# RS_MCU.net
KiCad netlist of a schematic drawn in Altium Designer
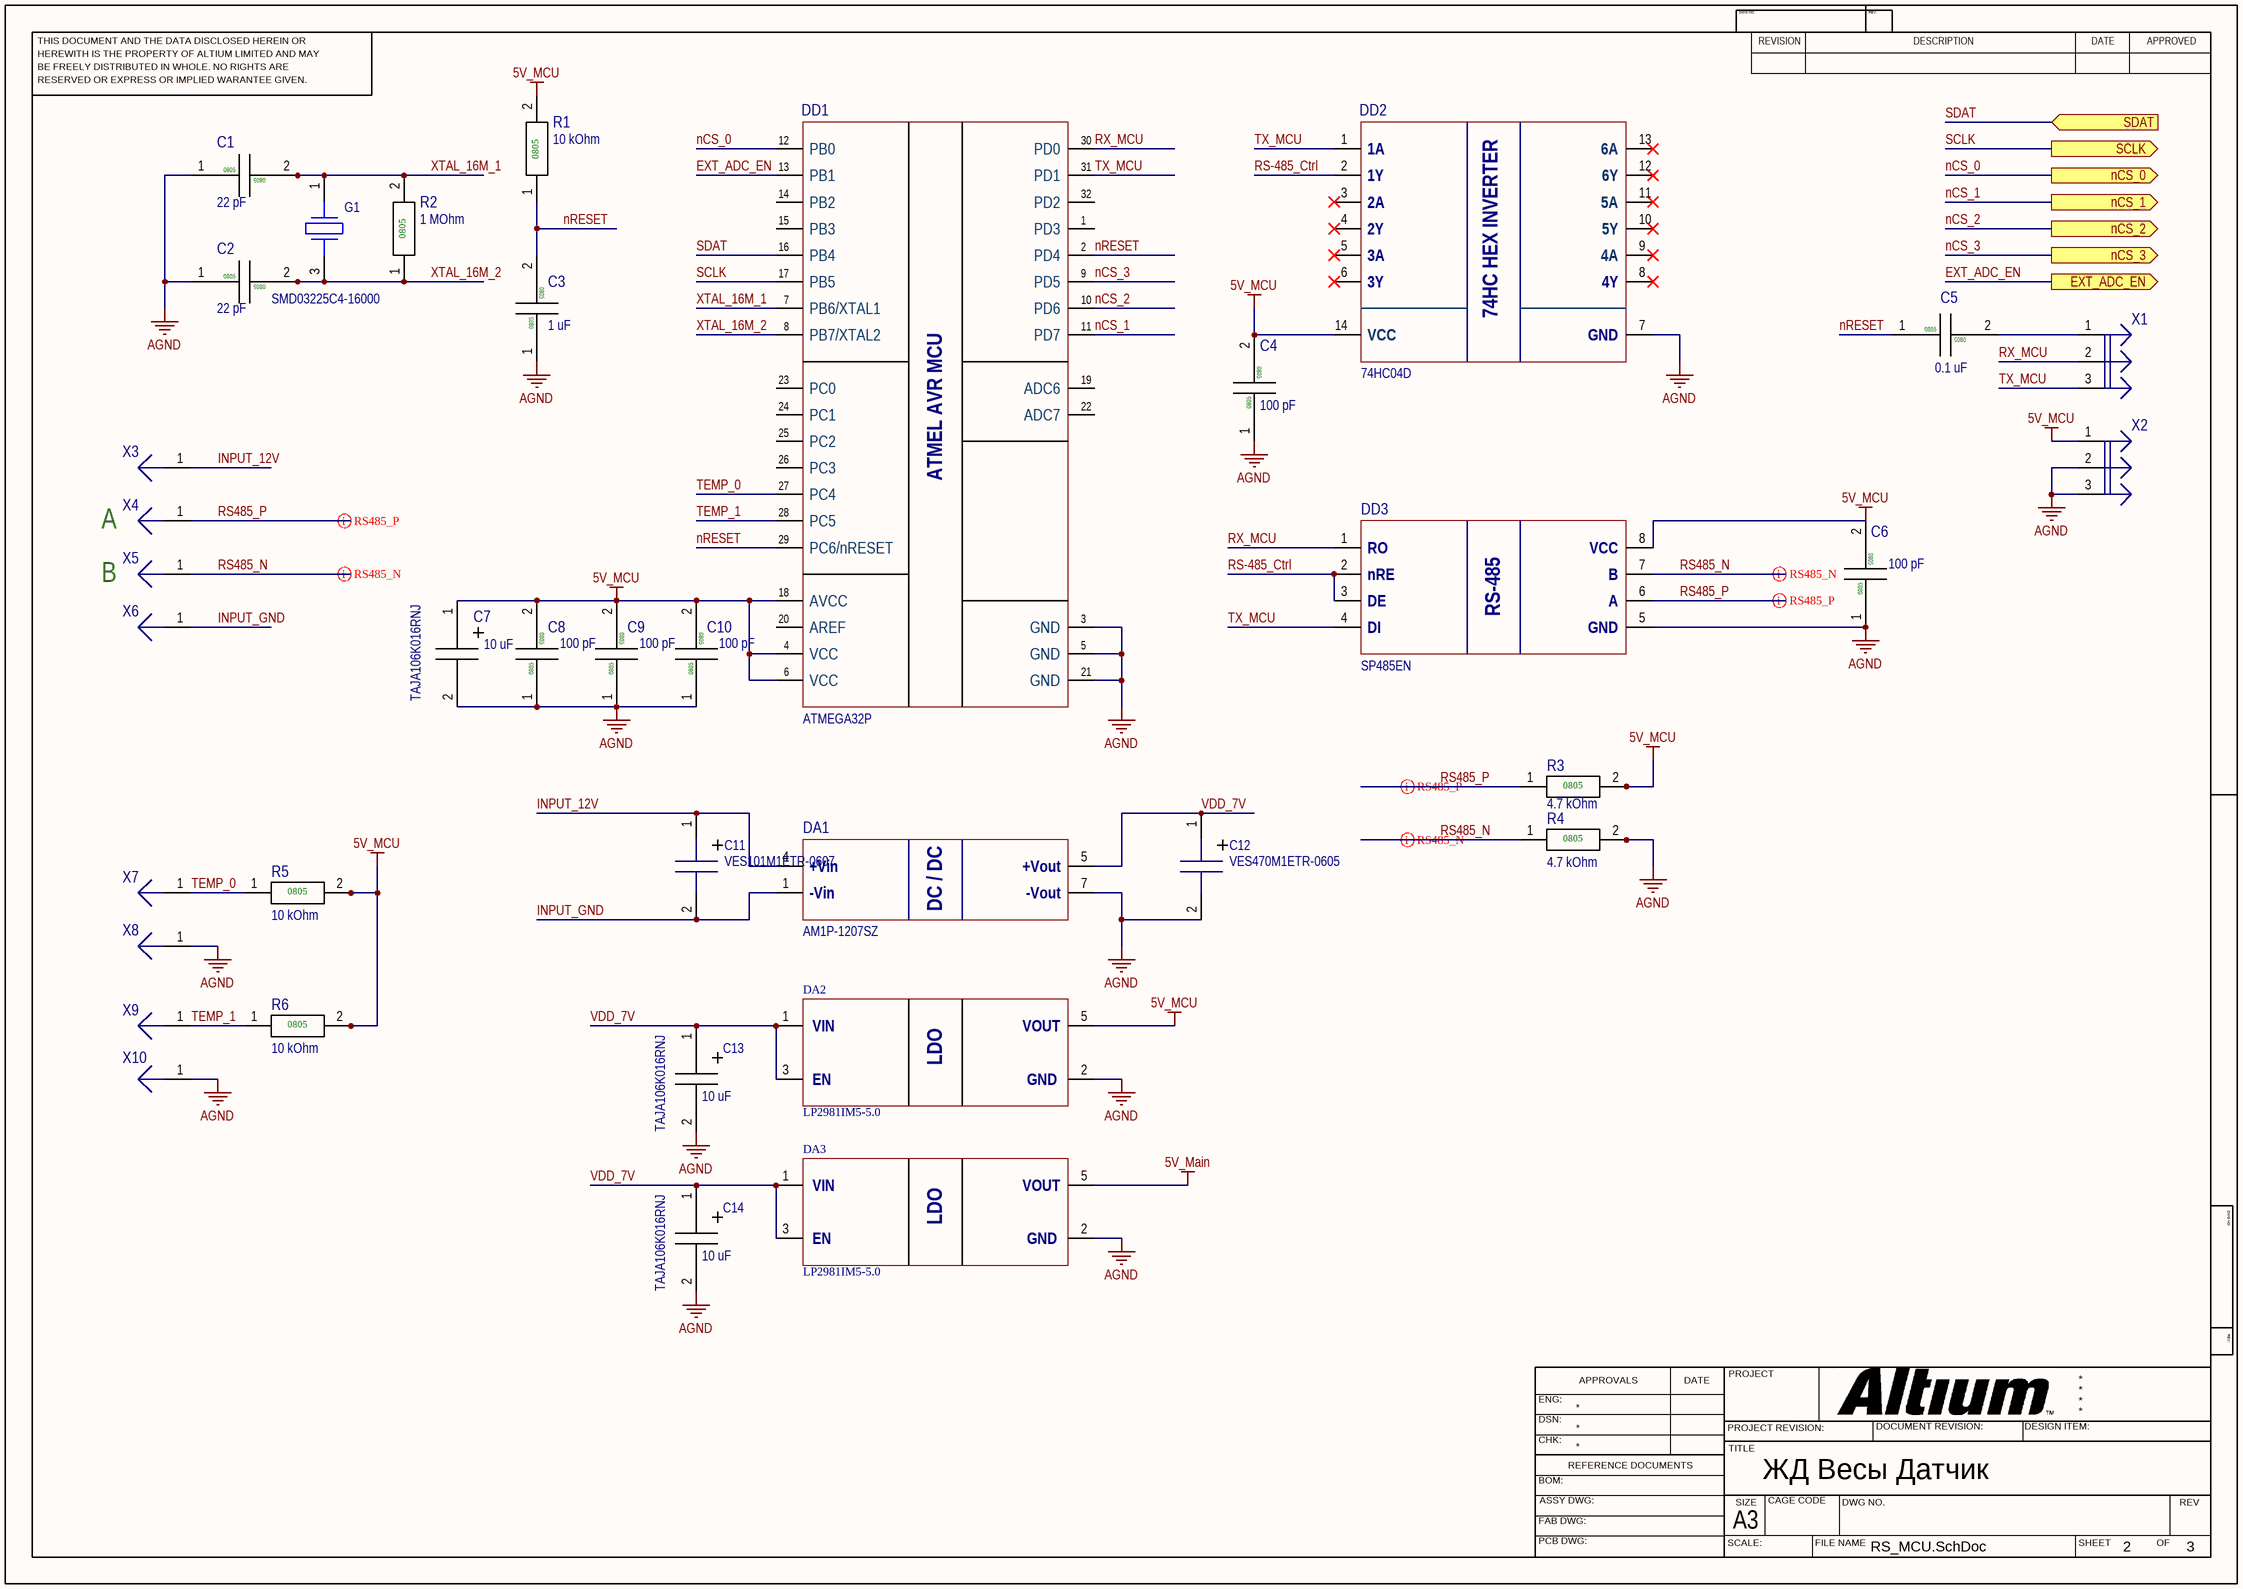
[diagram p0: RS_MCU.SchDoc]

(export (version "E")
  (design (tool "Eeschema 10.0.6"))
  (components
    (comp (ref "C1")
      (value "22 pF")
      (footprint "CAP: 0805")
      (description "50V 22pF C0G ±5% 0805 Multilayer Ceramic Capacitors MLCC - SMD/SMT ROHS")
      (fields
        (field (name "MANUFACTURER") "FH(Guangdong Fenghua Advanced Tech)")
        (field (name "VOLTAGE") "50 V")
      )
      (libsource (lib "CAP_Ceramic_0805(JLCPCB)") (part "22 pF 50V 5%"))
    )
    (comp (ref "C2")
      (value "22 pF")
      (footprint "CAP: 0805")
      (description "50V 22pF C0G ±5% 0805 Multilayer Ceramic Capacitors MLCC - SMD/SMT ROHS")
      (fields
        (field (name "MANUFACTURER") "FH(Guangdong Fenghua Advanced Tech)")
        (field (name "VOLTAGE") "50 V")
      )
      (libsource (lib "CAP_Ceramic_0805(JLCPCB)") (part "22 pF 50V 5%"))
    )
    (comp (ref "C3")
      (value "1 uF")
      (footprint "CAP: 0805")
      (description "Ceramic capacitor 0805 surface mount")
      (fields (field (name "MANUFACTURER") "Samsung Electro-Mechanics") (field (name "VOLTAGE") "50 V"))
      (libsource (lib "CAP_Ceramic_0805(JLCPCB)") (part "1 uF 50V 20%"))
    )
    (comp (ref "C4")
      (value "100 pF")
      (footprint "CAP: 0805")
      (description "Ceramic capacitor 0805 surface mount")
      (fields (field (name "MANUFACTURER") "Samsung Electro-Mechanics") (field (name "VOLTAGE") "50 V"))
      (libsource (lib "CAP_Ceramic_0805(JLCPCB)") (part "100 pF 50V 5%"))
    )
    (comp (ref "C5")
      (value "0.1 uF")
      (footprint "CAP: 0805")
      (description "Ceramic capacitor 0805 surface mount")
      (fields (field (name "MANUFACTURER") "Yageo") (field (name "VOLTAGE") "50 V"))
      (libsource (lib "CAP_Ceramic_0805(JLCPCB)") (part "0.1 uF 50V 20%"))
    )
    (comp (ref "C6")
      (value "100 pF")
      (footprint "CAP: 0805")
      (description "Ceramic capacitor 0805 surface mount")
      (fields (field (name "MANUFACTURER") "Samsung Electro-Mechanics") (field (name "VOLTAGE") "50 V"))
      (libsource (lib "CAP_Ceramic_0805(JLCPCB)") (part "100 pF 50V 5%"))
    )
    (comp (ref "C7")
      (value "TAJA106K016RNJ")
      (footprint "CAP: TANTAL-A")
      (description "10uF 16V 3Ω@100kHz -55℃~+125℃ ±10% CASE-A_3216 Tantalum Capacitors ROHS")
      (fields
        (field (name "MANUFACTURER") "AVX")
        (field (name "TOLERANCE") "10%")
        (field (name "CAPVALUE") "10 uF")
      )
      (libsource (lib "CAP_Tantalum") (part "10uF 16V 10%"))
    )
    (comp (ref "C8")
      (value "100 pF")
      (footprint "CAP: 0805")
      (description "Ceramic capacitor 0805 surface mount")
      (fields (field (name "MANUFACTURER") "Samsung Electro-Mechanics") (field (name "VOLTAGE") "50 V"))
      (libsource (lib "CAP_Ceramic_0805(JLCPCB)") (part "100 pF 50V 5%"))
    )
    (comp (ref "C9")
      (value "100 pF")
      (footprint "CAP: 0805")
      (description "Ceramic capacitor 0805 surface mount")
      (fields (field (name "MANUFACTURER") "Samsung Electro-Mechanics") (field (name "VOLTAGE") "50 V"))
      (libsource (lib "CAP_Ceramic_0805(JLCPCB)") (part "100 pF 50V 5%"))
    )
    (comp (ref "C10")
      (value "100 pF")
      (footprint "CAP: 0805")
      (description "Ceramic capacitor 0805 surface mount")
      (fields (field (name "MANUFACTURER") "Samsung Electro-Mechanics") (field (name "VOLTAGE") "50 V"))
      (libsource (lib "CAP_Ceramic_0805(JLCPCB)") (part "100 pF 50V 5%"))
    )
    (comp (ref "C11")
      (value "VES101M1ETR-0607")
      (footprint "CAPAE-C")
      (fields
        (field (name "LCSC PART NUMBER") "C176675")
        (field (name "MANUFACTURER") "Lelon")
        (field (name "VOLTAGE") "25 V")
      )
      (libsource (lib "CAP_Aluminium_SMD") (part "47uF 25V"))
    )
    (comp (ref "C12")
      (value "VES470M1ETR-0605")
      (footprint "CAPAE-C")
      (fields
        (field (name "LCSC PART NUMBER") "C176679")
        (field (name "MANUFACTURER") "Lelon")
        (field (name "VOLTAGE") "25 V")
      )
      (libsource (lib "CAP_Aluminium_SMD") (part "47uF 25V"))
    )
    (comp (ref "C13")
      (value "TAJA106K016RNJ")
      (footprint "CAP: TANTAL-A")
      (description "10uF 16V 3Ω@100kHz -55℃~+125℃ ±10% CASE-A_3216 Tantalum Capacitors ROHS")
      (fields
        (field (name "MANUFACTURER") "AVX")
        (field (name "TOLERANCE") "10%")
        (field (name "CAPVALUE") "10 uF")
      )
      (libsource (lib "CAP_Tantalum") (part "10uF 16V 10%"))
    )
    (comp (ref "C14")
      (value "TAJA106K016RNJ")
      (footprint "CAP: TANTAL-A")
      (description "10uF 16V 3Ω@100kHz -55℃~+125℃ ±10% CASE-A_3216 Tantalum Capacitors ROHS")
      (fields
        (field (name "MANUFACTURER") "AVX")
        (field (name "TOLERANCE") "10%")
        (field (name "CAPVALUE") "10 uF")
      )
      (libsource (lib "CAP_Tantalum") (part "10uF 16V 10%"))
    )
    (comp (ref "DA1")
      (value "AM1P-1207SZ")
      (footprint "MOD_AM1P-Z")
      (description "1W, FIXED INPUT, ISOLATED & REGULATED  SINGLE OUTPUT DC-DC CONVERTER")
      (fields (field (name "LCSC PART NUMBER") "--") (field (name "MANUFACTURER") "AIMTEC"))
      (libsource (lib "ICs_Power(Isolated)") (part "AM1P-1207SZ"))
    )
    (comp (ref "DA2")
      (value "LP2981IM5-5.0")
      (footprint "SOT-23-5")
      (description "Micropower 100-mA Ultralow Dropout Regulator in SOT-23 Package")
      (fields
        (field (name "MANUFACTURER") "Texas Instruments Incorporated")
        (field (name "LCSC PART NUMBER") "C3749295")
      )
      (libsource (lib "ICs_Power(Linear)") (part "LP2981IM5-5.0"))
    )
    (comp (ref "DA3")
      (value "LP2981IM5-5.0")
      (footprint "SOT-23-5")
      (description "Micropower 100-mA Ultralow Dropout Regulator in SOT-23 Package")
      (fields
        (field (name "MANUFACTURER") "Texas Instruments Incorporated")
        (field (name "LCSC PART NUMBER") "C3749295")
      )
      (libsource (lib "ICs_Power(Linear)") (part "LP2981IM5-5.0"))
    )
    (comp (ref "DD1")
      (value "ATMEGA32P")
      (footprint "32-LQFP")
      (fields (field (name "MANUFACTURER") "Atmel"))
      (libsource (lib "ICs_MCU") (part "ATMega238P"))
    )
    (comp (ref "DD2")
      (value "74HC04D")
      (footprint "14-SOIC")
      (fields (field (name "LCSC PART NUMBER") "C86613") (field (name "MANUFACTURER") "Shenzhen Fuman Elec"))
      (libsource (lib "ICs_Logic") (part "74HC04D"))
    )
    (comp (ref "DD3")
      (value "SP485EN")
      (footprint "8-SOIC")
      (description "Enhanced Low Power Half-Duplex\r\nRS-485 Transceivers")
      (fields
        (field (name "MANUFACTURER") "UMW(Youtai Semiconductor Co., Ltd.")
        (field (name "LCSC PART NUMBER") "C23492")
      )
      (libsource (lib "ICs_Interface") (part "SP485EN"))
    )
    (comp (ref "G1")
      (value "SMD03225C4-16000")
      (footprint "OSC: 3225")
      (description "Crystals WE-XTAL 16.0MHz 50ppm 13.4 x 4.9mm")
      (fields (field (name "MANUFACTURER") "SDE"))
      (libsource (lib "Crystals") (part "SMD03225C4-16000"))
    )
    (comp (ref "R1")
      (value "10 kOhm")
      (footprint "RES: 0805")
      (description "LEAD-FREE THICK FILM CHIP RESISTORS")
      (fields (field (name "MANUFACTURER") "Uniroyal Elec") (field (name "TOLERANCE") "1%"))
      (libsource (lib "") (part "10k 1% 1/8W_1"))
    )
    (comp (ref "R2")
      (value "1 MOhm")
      (footprint "RES: 0805")
      (description "LEAD-FREE THICK FILM CHIP RESISTORS")
      (fields (field (name "MANUFACTURER") "Uniroyal Elec") (field (name "TOLERANCE") "1%"))
      (libsource (lib "RES_SMD_0805(JLCPCB)") (part "1M 1% 1/8W"))
    )
    (comp (ref "R3")
      (value "4.7 kOhm")
      (footprint "RES: 0805")
      (description "LEAD-FREE THICK FILM CHIP RESISTORS")
      (fields (field (name "MANUFACTURER") "Uniroyal Elec") (field (name "TOLERANCE") "1%"))
      (libsource (lib "RES_SMD_0805(JLCPCB)") (part "4.7k 1% 1/8W"))
    )
    (comp (ref "R4")
      (value "4.7 kOhm")
      (footprint "RES: 0805")
      (description "LEAD-FREE THICK FILM CHIP RESISTORS")
      (fields (field (name "MANUFACTURER") "Uniroyal Elec") (field (name "TOLERANCE") "1%"))
      (libsource (lib "RES_SMD_0805(JLCPCB)") (part "4.7k 1% 1/8W"))
    )
    (comp (ref "R5")
      (value "10 kOhm")
      (footprint "RES: 0805")
      (description "LEAD-FREE THICK FILM CHIP RESISTORS")
      (fields (field (name "MANUFACTURER") "Uniroyal Elec") (field (name "TOLERANCE") "1%"))
      (libsource (lib "RES_SMD_0805(JLCPCB)") (part "10k 1% 1/8W"))
    )
    (comp (ref "R6")
      (value "10 kOhm")
      (footprint "RES: 0805")
      (description "LEAD-FREE THICK FILM CHIP RESISTORS")
      (fields (field (name "MANUFACTURER") "Uniroyal Elec") (field (name "TOLERANCE") "1%"))
      (libsource (lib "RES_SMD_0805(JLCPCB)") (part "10k 1% 1/8W"))
    )
    (comp (ref "X1")
      (value "PLS-1X3Pin 2.54")
      (footprint "CON: PLS-3")
      (libsource (lib "Connectors&PinHeaders") (part "PLS-1X3Pin 2.54"))
    )
    (comp (ref "X2")
      (value "PLS-1X3Pin 2.54")
      (footprint "CON: PLS-3")
      (libsource (lib "Connectors&PinHeaders") (part "PLS-1X3Pin 2.54"))
    )
    (comp (ref "X3")
      (value "PowerSingleHole")
      (footprint "PowerSingle")
      (libsource (lib "Connectors&PinHeaders") (part "PowerSingleHole"))
    )
    (comp (ref "X4")
      (value "PowerSingleHole")
      (footprint "PowerSingle")
      (libsource (lib "Connectors&PinHeaders") (part "PowerSingleHole"))
    )
    (comp (ref "X5")
      (value "PowerSingleHole")
      (footprint "PowerSingle")
      (libsource (lib "Connectors&PinHeaders") (part "PowerSingleHole"))
    )
    (comp (ref "X6")
      (value "PowerSingleHole")
      (footprint "PowerSingle")
      (libsource (lib "Connectors&PinHeaders") (part "PowerSingleHole"))
    )
    (comp (ref "X7")
      (value "PowerSingleHole")
      (footprint "PowerSingle")
      (libsource (lib "Connectors&PinHeaders") (part "PowerSingleHole"))
    )
    (comp (ref "X8")
      (value "PowerSingleHole")
      (footprint "PowerSingle")
      (libsource (lib "Connectors&PinHeaders") (part "PowerSingleHole"))
    )
    (comp (ref "X9")
      (value "PowerSingleHole")
      (footprint "PowerSingle")
      (libsource (lib "Connectors&PinHeaders") (part "PowerSingleHole"))
    )
    (comp (ref "X10")
      (value "PowerSingleHole")
      (footprint "PowerSingle")
      (libsource (lib "Connectors&PinHeaders") (part "PowerSingleHole"))
    )
  )
  (nets
    (net (code "1") (name "/EXT_ADC_EN") (class "Default")
      (node (ref "DD1") (pin "13") (pinfunction "PB1_13") (pintype "passive"))
    )
    (net (code "2") (name "/INPUT_12V") (class "Default")
      (node (ref "C11") (pin "1") (pintype "passive"))
      (node (ref "DA1") (pin "4") (pinfunction "+Vin_4") (pintype "passive"))
      (node (ref "X3") (pin "1") (pinfunction "1_1") (pintype "passive"))
    )
    (net (code "3") (name "/INPUT_GND") (class "Default")
      (node (ref "C11") (pin "2") (pintype "passive"))
      (node (ref "DA1") (pin "1") (pinfunction "-Vin_1") (pintype "passive"))
      (node (ref "X6") (pin "1") (pinfunction "1_1") (pintype "passive"))
    )
    (net (code "4") (name "/RS-485_Ctrl") (class "Default")
      (node (ref "DD2") (pin "2") (pinfunction "1Y_2") (pintype "passive"))
      (node (ref "DD3") (pin "2") (pinfunction "nRE_2") (pintype "passive"))
      (node (ref "DD3") (pin "3") (pinfunction "DE_3") (pintype "passive"))
    )
    (net (code "5") (name "/RS485_N") (class "Default")
      (node (ref "DD3") (pin "7") (pinfunction "B_7") (pintype "passive"))
      (node (ref "R4") (pin "1") (pintype "passive"))
      (node (ref "X5") (pin "1") (pinfunction "1_1") (pintype "passive"))
    )
    (net (code "6") (name "/RS485_P") (class "Default")
      (node (ref "DD3") (pin "6") (pinfunction "A_6") (pintype "passive"))
      (node (ref "R3") (pin "1") (pintype "passive"))
      (node (ref "X4") (pin "1") (pinfunction "1_1") (pintype "passive"))
    )
    (net (code "7") (name "/RX_MCU") (class "Default")
      (node (ref "DD1") (pin "30") (pinfunction "PD0_30") (pintype "passive"))
      (node (ref "DD3") (pin "1") (pinfunction "RO_1") (pintype "passive"))
      (node (ref "X1") (pin "2") (pinfunction "2_2") (pintype "passive"))
    )
    (net (code "8") (name "/SCLK") (class "Default")
      (node (ref "DD1") (pin "17") (pinfunction "PB5_17") (pintype "passive"))
    )
    (net (code "9") (name "/SDAT") (class "Default")
      (node (ref "DD1") (pin "16") (pinfunction "PB4_16") (pintype "passive"))
    )
    (net (code "10") (name "/TEMP_0") (class "Default")
      (node (ref "DD1") (pin "27") (pinfunction "PC4_27") (pintype "passive"))
      (node (ref "R5") (pin "1") (pintype "passive"))
      (node (ref "X7") (pin "1") (pinfunction "1_1") (pintype "passive"))
    )
    (net (code "11") (name "/TEMP_1") (class "Default")
      (node (ref "DD1") (pin "28") (pinfunction "PC5_28") (pintype "passive"))
      (node (ref "R6") (pin "1") (pintype "passive"))
      (node (ref "X9") (pin "1") (pinfunction "1_1") (pintype "passive"))
    )
    (net (code "12") (name "/TX_MCU") (class "Default")
      (node (ref "DD1") (pin "31") (pinfunction "PD1_31") (pintype "passive"))
      (node (ref "DD2") (pin "1") (pinfunction "1A_1") (pintype "passive"))
      (node (ref "DD3") (pin "4") (pinfunction "DI_4") (pintype "passive"))
      (node (ref "X1") (pin "3") (pinfunction "3_3") (pintype "passive"))
    )
    (net (code "13") (name "/VDD_7V") (class "Default")
      (node (ref "C12") (pin "1") (pintype "passive"))
      (node (ref "C13") (pin "1") (pintype "passive"))
      (node (ref "C14") (pin "1") (pintype "passive"))
      (node (ref "DA1") (pin "5") (pinfunction "+Vout_5") (pintype "passive"))
      (node (ref "DA2") (pin "1") (pinfunction "VIN_1") (pintype "passive"))
      (node (ref "DA2") (pin "3") (pinfunction "EN_3") (pintype "passive"))
      (node (ref "DA3") (pin "1") (pinfunction "VIN_1") (pintype "passive"))
      (node (ref "DA3") (pin "3") (pinfunction "EN_3") (pintype "passive"))
    )
    (net (code "14") (name "/XTAL_16M_1") (class "Default")
      (node (ref "C1") (pin "2") (pintype "passive"))
      (node (ref "DD1") (pin "7") (pinfunction "PB6/XTAL1_7") (pintype "passive"))
      (node (ref "G1") (pin "1") (pintype "passive"))
      (node (ref "R2") (pin "2") (pintype "passive"))
    )
    (net (code "15") (name "/XTAL_16M_2") (class "Default")
      (node (ref "C2") (pin "2") (pintype "passive"))
      (node (ref "DD1") (pin "8") (pinfunction "PB7/XTAL2_8") (pintype "passive"))
      (node (ref "G1") (pin "3") (pintype "passive"))
      (node (ref "R2") (pin "1") (pintype "passive"))
    )
    (net (code "16") (name "/nCS_0") (class "Default")
      (node (ref "DD1") (pin "12") (pinfunction "PB0_12") (pintype "passive"))
    )
    (net (code "17") (name "/nCS_1") (class "Default")
      (node (ref "DD1") (pin "11") (pinfunction "PD7_11") (pintype "passive"))
    )
    (net (code "18") (name "/nCS_2") (class "Default")
      (node (ref "DD1") (pin "10") (pinfunction "PD6_10") (pintype "passive"))
    )
    (net (code "19") (name "/nCS_3") (class "Default")
      (node (ref "DD1") (pin "9") (pinfunction "PD5_9") (pintype "passive"))
    )
    (net (code "20") (name "/nRESET") (class "Default")
      (node (ref "C3") (pin "2") (pintype "passive"))
      (node (ref "C5") (pin "1") (pintype "passive"))
      (node (ref "DD1") (pin "2") (pinfunction "PD4_2") (pintype "passive"))
      (node (ref "DD1") (pin "29") (pinfunction "PC6/nRESET_29") (pintype "passive"))
      (node (ref "R1") (pin "1") (pintype "passive"))
    )
    (net (code "21") (name "5V_MCU") (class "Default")
      (node (ref "C10") (pin "2") (pintype "passive"))
      (node (ref "C4") (pin "2") (pintype "passive"))
      (node (ref "C6") (pin "2") (pintype "passive"))
      (node (ref "C7") (pin "1") (pintype "passive"))
      (node (ref "C8") (pin "2") (pintype "passive"))
      (node (ref "C9") (pin "2") (pintype "passive"))
      (node (ref "DA2") (pin "5") (pinfunction "VOUT_5") (pintype "passive"))
      (node (ref "DD1") (pin "18") (pinfunction "AVCC_18") (pintype "passive"))
      (node (ref "DD1") (pin "4") (pinfunction "VCC_4") (pintype "passive"))
      (node (ref "DD1") (pin "6") (pinfunction "VCC_6") (pintype "passive"))
      (node (ref "DD2") (pin "14") (pinfunction "VCC_14") (pintype "passive"))
      (node (ref "DD3") (pin "8") (pinfunction "VCC_8") (pintype "passive"))
      (node (ref "R1") (pin "2") (pintype "passive"))
      (node (ref "R3") (pin "2") (pintype "passive"))
      (node (ref "R5") (pin "2") (pintype "passive"))
      (node (ref "R6") (pin "2") (pintype "passive"))
      (node (ref "X2") (pin "1") (pinfunction "1_1") (pintype "passive"))
    )
    (net (code "22") (name "5V_Main") (class "Default")
      (node (ref "DA3") (pin "5") (pinfunction "VOUT_5") (pintype "passive"))
    )
    (net (code "23") (name "AGND") (class "Default")
      (node (ref "C1") (pin "1") (pintype "passive"))
      (node (ref "C10") (pin "1") (pintype "passive"))
      (node (ref "C12") (pin "2") (pintype "passive"))
      (node (ref "C13") (pin "2") (pintype "passive"))
      (node (ref "C14") (pin "2") (pintype "passive"))
      (node (ref "C2") (pin "1") (pintype "passive"))
      (node (ref "C3") (pin "1") (pintype "passive"))
      (node (ref "C4") (pin "1") (pintype "passive"))
      (node (ref "C6") (pin "1") (pintype "passive"))
      (node (ref "C7") (pin "2") (pintype "passive"))
      (node (ref "C8") (pin "1") (pintype "passive"))
      (node (ref "C9") (pin "1") (pintype "passive"))
      (node (ref "DA1") (pin "7") (pinfunction "-Vout_7") (pintype "passive"))
      (node (ref "DA2") (pin "2") (pinfunction "GND_2") (pintype "passive"))
      (node (ref "DA3") (pin "2") (pinfunction "GND_2") (pintype "passive"))
      (node (ref "DD1") (pin "21") (pinfunction "GND_21") (pintype "passive"))
      (node (ref "DD1") (pin "3") (pinfunction "GND_3") (pintype "passive"))
      (node (ref "DD1") (pin "5") (pinfunction "GND_5") (pintype "passive"))
      (node (ref "DD2") (pin "7") (pinfunction "GND_7") (pintype "passive"))
      (node (ref "DD3") (pin "5") (pinfunction "GND_5") (pintype "passive"))
      (node (ref "R4") (pin "2") (pintype "passive"))
      (node (ref "X10") (pin "1") (pinfunction "1_1") (pintype "passive"))
      (node (ref "X2") (pin "2") (pinfunction "2_2") (pintype "passive"))
      (node (ref "X2") (pin "3") (pinfunction "3_3") (pintype "passive"))
      (node (ref "X8") (pin "1") (pinfunction "1_1") (pintype "passive"))
    )
    (net (code "24") (name "Net-(C5-Pad2)") (class "Default")
      (node (ref "C5") (pin "2") (pintype "passive"))
      (node (ref "X1") (pin "1") (pinfunction "1_1") (pintype "passive"))
    )
    (net (code "25") (name "unconnected-(DD1-ADC6-Pad19)") (class "Default")
      (node (ref "DD1") (pin "19") (pinfunction "ADC6_19") (pintype "passive"))
    )
    (net (code "26") (name "unconnected-(DD1-ADC7-Pad22)") (class "Default")
      (node (ref "DD1") (pin "22") (pinfunction "ADC7_22") (pintype "passive"))
    )
    (net (code "27") (name "unconnected-(DD1-AREF-Pad20)") (class "Default")
      (node (ref "DD1") (pin "20") (pinfunction "AREF_20") (pintype "passive"))
    )
    (net (code "28") (name "unconnected-(DD1-PB2-Pad14)") (class "Default")
      (node (ref "DD1") (pin "14") (pinfunction "PB2_14") (pintype "passive"))
    )
    (net (code "29") (name "unconnected-(DD1-PB3-Pad15)") (class "Default")
      (node (ref "DD1") (pin "15") (pinfunction "PB3_15") (pintype "passive"))
    )
    (net (code "30") (name "unconnected-(DD1-PC0-Pad23)") (class "Default")
      (node (ref "DD1") (pin "23") (pinfunction "PC0_23") (pintype "passive"))
    )
    (net (code "31") (name "unconnected-(DD1-PC1-Pad24)") (class "Default")
      (node (ref "DD1") (pin "24") (pinfunction "PC1_24") (pintype "passive"))
    )
    (net (code "32") (name "unconnected-(DD1-PC2-Pad25)") (class "Default")
      (node (ref "DD1") (pin "25") (pinfunction "PC2_25") (pintype "passive"))
    )
    (net (code "33") (name "unconnected-(DD1-PC3-Pad26)") (class "Default")
      (node (ref "DD1") (pin "26") (pinfunction "PC3_26") (pintype "passive"))
    )
    (net (code "34") (name "unconnected-(DD1-PD2-Pad32)") (class "Default")
      (node (ref "DD1") (pin "32") (pinfunction "PD2_32") (pintype "passive"))
    )
    (net (code "35") (name "unconnected-(DD1-PD3-Pad1)") (class "Default")
      (node (ref "DD1") (pin "1") (pinfunction "PD3_1") (pintype "passive"))
    )
    (net (code "36") (name "unconnected-(DD2-2A-Pad3)") (class "Default")
      (node (ref "DD2") (pin "3") (pinfunction "2A_3") (pintype "passive+no_connect"))
    )
    (net (code "37") (name "unconnected-(DD2-2Y-Pad4)") (class "Default")
      (node (ref "DD2") (pin "4") (pinfunction "2Y_4") (pintype "passive+no_connect"))
    )
    (net (code "38") (name "unconnected-(DD2-3A-Pad5)") (class "Default")
      (node (ref "DD2") (pin "5") (pinfunction "3A_5") (pintype "passive+no_connect"))
    )
    (net (code "39") (name "unconnected-(DD2-3Y-Pad6)") (class "Default")
      (node (ref "DD2") (pin "6") (pinfunction "3Y_6") (pintype "passive+no_connect"))
    )
    (net (code "40") (name "unconnected-(DD2-4A-Pad9)") (class "Default")
      (node (ref "DD2") (pin "9") (pinfunction "4A_9") (pintype "passive+no_connect"))
    )
    (net (code "41") (name "unconnected-(DD2-4Y-Pad8)") (class "Default")
      (node (ref "DD2") (pin "8") (pinfunction "4Y_8") (pintype "passive+no_connect"))
    )
    (net (code "42") (name "unconnected-(DD2-5A-Pad11)") (class "Default")
      (node (ref "DD2") (pin "11") (pinfunction "5A_11") (pintype "passive+no_connect"))
    )
    (net (code "43") (name "unconnected-(DD2-5Y-Pad10)") (class "Default")
      (node (ref "DD2") (pin "10") (pinfunction "5Y_10") (pintype "passive+no_connect"))
    )
    (net (code "44") (name "unconnected-(DD2-6A-Pad13)") (class "Default")
      (node (ref "DD2") (pin "13") (pinfunction "6A_13") (pintype "passive+no_connect"))
    )
    (net (code "45") (name "unconnected-(DD2-6Y-Pad12)") (class "Default")
      (node (ref "DD2") (pin "12") (pinfunction "6Y_12") (pintype "passive+no_connect"))
    )
  )
)
